# DASH_V_3_LEDS_POWER.net
KiCad netlist of a schematic drawn in Altium Designer
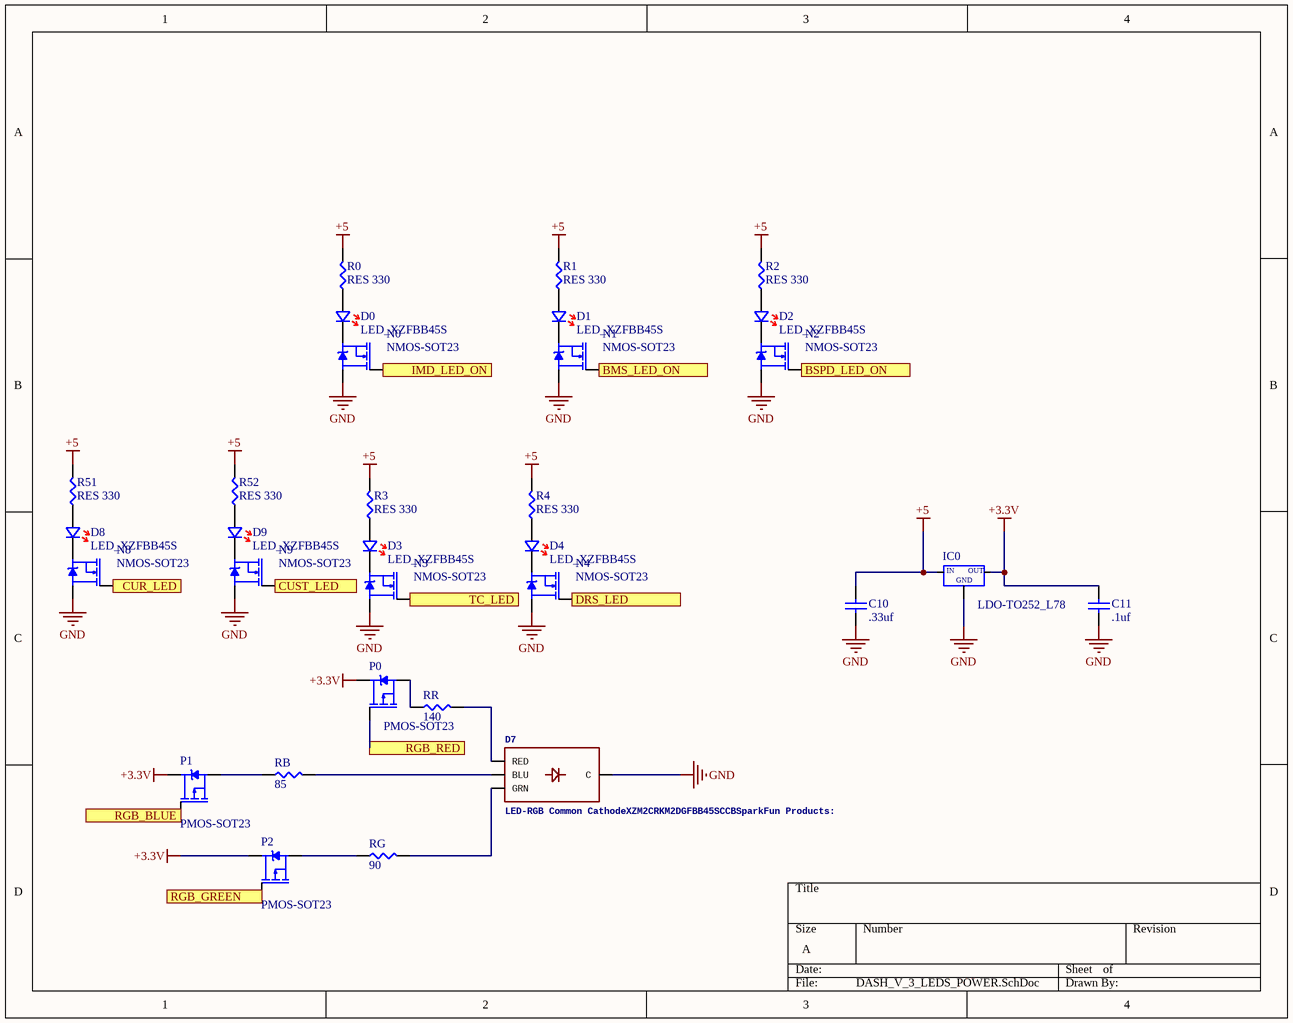
[diagram p0: DASH_V_3_LEDS_POWER.SchDoc]

(export (version "E")
  (design (tool "Eeschema 10.0.6"))
  (components
    (comp (ref "C10")
      (value ".33uf")
      (footprint "CAPC1608X87X35NL15T15")
      (description ".1 uf")
      (fields (field (name "PART NUMBER") "C0603C104J3RAC7867") (field (name "MANUFACTURER") "Kemet"))
      (libsource (lib "Altium Content Vault") (part "CAP"))
    )
    (comp (ref "C11")
      (value ".1uf")
      (footprint "CAPC1608X87X35NL15T15")
      (description ".1 uf")
      (fields (field (name "PART NUMBER") "C0603C104J3RAC7867") (field (name "MANUFACTURER") "Kemet"))
      (libsource (lib "Altium Content Vault") (part "CAP"))
    )
    (comp (ref "D0")
      (value "LED_XZFBB45S")
      (footprint "LED_XZFBB45S")
      (libsource (lib "ife19_Elec_Library") (part "LED_XZFBB45S"))
    )
    (comp (ref "D1")
      (value "LED_XZFBB45S")
      (footprint "LED_XZFBB45S")
      (libsource (lib "ife19_Elec_Library") (part "LED_XZFBB45S"))
    )
    (comp (ref "D2")
      (value "LED_XZFBB45S")
      (footprint "LED_XZFBB45S")
      (libsource (lib "ife19_Elec_Library") (part "LED_XZFBB45S"))
    )
    (comp (ref "D3")
      (value "LED_XZFBB45S")
      (footprint "LED_XZFBB45S")
      (libsource (lib "ife19_Elec_Library") (part "LED_XZFBB45S"))
    )
    (comp (ref "D4")
      (value "LED_XZFBB45S")
      (footprint "LED_XZFBB45S")
      (libsource (lib "ife19_Elec_Library") (part "LED_XZFBB45S"))
    )
    (comp (ref "D7")
      (value "LED-RGB Common CathodeXZM2CRKM2DGFBB45SCCBSparkFun Products:")
      (footprint "PLCC4SMDLED")
      (libsource (lib "SparkFun-LED") (part "SUNLEDSMD1"))
    )
    (comp (ref "D8")
      (value "LED_XZFBB45S")
      (footprint "LED_XZFBB45S")
      (libsource (lib "ife19_Elec_Library") (part "LED_XZFBB45S"))
    )
    (comp (ref "D9")
      (value "LED_XZFBB45S")
      (footprint "LED_XZFBB45S")
      (libsource (lib "ife19_Elec_Library") (part "LED_XZFBB45S"))
    )
    (comp (ref "IC0")
      (value "LDO-TO252_L78")
      (footprint "TO252")
      (libsource (lib "ife19_Elec_Library") (part "LDO-TO252_L78"))
    )
    (comp (ref "N0")
      (value "NMOS-SOT23")
      (footprint "SOT23")
      (libsource (lib "ife19_Elec_Library") (part "NMOS-SOT23"))
    )
    (comp (ref "N1")
      (value "NMOS-SOT23")
      (footprint "SOT23")
      (libsource (lib "ife19_Elec_Library") (part "NMOS-SOT23"))
    )
    (comp (ref "N2")
      (value "NMOS-SOT23")
      (footprint "SOT23")
      (libsource (lib "ife19_Elec_Library") (part "NMOS-SOT23"))
    )
    (comp (ref "N3")
      (value "NMOS-SOT23")
      (footprint "SOT23")
      (libsource (lib "ife19_Elec_Library") (part "NMOS-SOT23"))
    )
    (comp (ref "N4")
      (value "NMOS-SOT23")
      (footprint "SOT23")
      (libsource (lib "ife19_Elec_Library") (part "NMOS-SOT23"))
    )
    (comp (ref "N8")
      (value "NMOS-SOT23")
      (footprint "SOT23")
      (libsource (lib "ife19_Elec_Library") (part "NMOS-SOT23"))
    )
    (comp (ref "N9")
      (value "NMOS-SOT23")
      (footprint "SOT23")
      (libsource (lib "ife19_Elec_Library") (part "NMOS-SOT23"))
    )
    (comp (ref "P0")
      (value "PMOS-SOT23")
      (footprint "SOT23")
      (libsource (lib "ife19_Elec_Library") (part "PMOS-SOT23"))
    )
    (comp (ref "P1")
      (value "PMOS-SOT23")
      (footprint "SOT23")
      (libsource (lib "ife19_Elec_Library") (part "PMOS-SOT23"))
    )
    (comp (ref "P2")
      (value "PMOS-SOT23")
      (footprint "SOT23")
      (libsource (lib "ife19_Elec_Library") (part "PMOS-SOT23"))
    )
    (comp (ref "R0")
      (value "RES 330")
      (footprint "RES-0603")
      (libsource (lib "ife19_Elec_Library") (part "RES-0603"))
    )
    (comp (ref "R1")
      (value "RES 330")
      (footprint "RES-0603")
      (libsource (lib "ife19_Elec_Library") (part "RES-0603"))
    )
    (comp (ref "R2")
      (value "RES 330")
      (footprint "RES-0603")
      (libsource (lib "ife19_Elec_Library") (part "RES-0603"))
    )
    (comp (ref "R3")
      (value "RES 330")
      (footprint "RES-0603")
      (libsource (lib "ife19_Elec_Library") (part "RES-0603"))
    )
    (comp (ref "R4")
      (value "RES 330")
      (footprint "RES-0603")
      (libsource (lib "ife19_Elec_Library") (part "RES-0603"))
    )
    (comp (ref "R51")
      (value "RES 330")
      (footprint "RES-0603")
      (libsource (lib "ife19_Elec_Library") (part "RES-0603"))
    )
    (comp (ref "R52")
      (value "RES 330")
      (footprint "RES-0603")
      (libsource (lib "ife19_Elec_Library") (part "RES-0603"))
    )
    (comp (ref "RB")
      (value "85")
      (footprint "RES-0603")
      (libsource (lib "ife19_Elec_Library") (part "RES-0603"))
    )
    (comp (ref "RG")
      (value "90")
      (footprint "RES-0603")
      (libsource (lib "ife19_Elec_Library") (part "RES-0603"))
    )
    (comp (ref "RR")
      (value "140")
      (footprint "RES-0603")
      (libsource (lib "ife19_Elec_Library") (part "RES-0603"))
    )
  )
  (nets
    (net (code "1") (name "+3.3V") (class "Default")
      (node (ref "C11") (pin "2") (pinfunction "2_2") (pintype "passive"))
      (node (ref "IC0") (pin "3") (pinfunction "22_3") (pintype "passive"))
      (node (ref "P0") (pin "2") (pinfunction "S_2") (pintype "passive"))
      (node (ref "P1") (pin "2") (pinfunction "S_2") (pintype "passive"))
      (node (ref "P2") (pin "2") (pinfunction "S_2") (pintype "passive"))
    )
    (net (code "2") (name "+5") (class "Default")
      (node (ref "C10") (pin "2") (pinfunction "2_2") (pintype "passive"))
      (node (ref "IC0") (pin "1") (pinfunction "21_1") (pintype "passive"))
      (node (ref "R0") (pin "2") (pinfunction "2_2") (pintype "passive"))
      (node (ref "R1") (pin "2") (pinfunction "2_2") (pintype "passive"))
      (node (ref "R2") (pin "2") (pinfunction "2_2") (pintype "passive"))
      (node (ref "R3") (pin "2") (pinfunction "2_2") (pintype "passive"))
      (node (ref "R4") (pin "2") (pinfunction "2_2") (pintype "passive"))
      (node (ref "R51") (pin "2") (pinfunction "2_2") (pintype "passive"))
      (node (ref "R52") (pin "2") (pinfunction "2_2") (pintype "passive"))
    )
    (net (code "3") (name "/BMS_LED_ON") (class "Default")
      (node (ref "N1") (pin "1") (pinfunction "G_1") (pintype "passive"))
    )
    (net (code "4") (name "/BSPD_LED_ON") (class "Default")
      (node (ref "N2") (pin "1") (pinfunction "G_1") (pintype "passive"))
    )
    (net (code "5") (name "/CUR_LED") (class "Default")
      (node (ref "N8") (pin "1") (pinfunction "G_1") (pintype "passive"))
    )
    (net (code "6") (name "/CUST_LED") (class "Default")
      (node (ref "N9") (pin "1") (pinfunction "G_1") (pintype "passive"))
    )
    (net (code "7") (name "/DRS_LED") (class "Default")
      (node (ref "N4") (pin "1") (pinfunction "G_1") (pintype "passive"))
    )
    (net (code "8") (name "/IMD_LED_ON") (class "Default")
      (node (ref "N0") (pin "1") (pinfunction "G_1") (pintype "passive"))
    )
    (net (code "9") (name "/RGB_BLUE") (class "Default")
      (node (ref "P1") (pin "1") (pinfunction "G_1") (pintype "passive"))
    )
    (net (code "10") (name "/RGB_GREEN") (class "Default")
      (node (ref "P2") (pin "1") (pinfunction "G_1") (pintype "passive"))
    )
    (net (code "11") (name "/RGB_RED") (class "Default")
      (node (ref "P0") (pin "1") (pinfunction "G_1") (pintype "passive"))
    )
    (net (code "12") (name "/TC_LED") (class "Default")
      (node (ref "N3") (pin "1") (pinfunction "G_1") (pintype "passive"))
    )
    (net (code "13") (name "GND") (class "Default")
      (node (ref "C10") (pin "1") (pinfunction "1_1") (pintype "passive"))
      (node (ref "C11") (pin "1") (pinfunction "1_1") (pintype "passive"))
      (node (ref "D7") (pin "4") (pinfunction "C_4") (pintype "passive"))
      (node (ref "IC0") (pin "2") (pinfunction "23_2") (pintype "passive"))
      (node (ref "N0") (pin "2") (pinfunction "S_2") (pintype "passive"))
      (node (ref "N1") (pin "2") (pinfunction "S_2") (pintype "passive"))
      (node (ref "N2") (pin "2") (pinfunction "S_2") (pintype "passive"))
      (node (ref "N3") (pin "2") (pinfunction "S_2") (pintype "passive"))
      (node (ref "N4") (pin "2") (pinfunction "S_2") (pintype "passive"))
      (node (ref "N8") (pin "2") (pinfunction "S_2") (pintype "passive"))
      (node (ref "N9") (pin "2") (pinfunction "S_2") (pintype "passive"))
    )
    (net (code "14") (name "Net-(D0-PadA)") (class "Default")
      (node (ref "D0") (pin "A") (pinfunction "A_A") (pintype "passive"))
      (node (ref "R0") (pin "1") (pinfunction "1_1") (pintype "passive"))
    )
    (net (code "15") (name "Net-(D1-PadA)") (class "Default")
      (node (ref "D1") (pin "A") (pinfunction "A_A") (pintype "passive"))
      (node (ref "R1") (pin "1") (pinfunction "1_1") (pintype "passive"))
    )
    (net (code "16") (name "Net-(D2-PadA)") (class "Default")
      (node (ref "D2") (pin "A") (pinfunction "A_A") (pintype "passive"))
      (node (ref "R2") (pin "1") (pinfunction "1_1") (pintype "passive"))
    )
    (net (code "17") (name "Net-(D3-PadA)") (class "Default")
      (node (ref "D3") (pin "A") (pinfunction "A_A") (pintype "passive"))
      (node (ref "R3") (pin "1") (pinfunction "1_1") (pintype "passive"))
    )
    (net (code "18") (name "Net-(D4-PadA)") (class "Default")
      (node (ref "D4") (pin "A") (pinfunction "A_A") (pintype "passive"))
      (node (ref "R4") (pin "1") (pinfunction "1_1") (pintype "passive"))
    )
    (net (code "19") (name "Net-(D7-BLU)") (class "Default")
      (node (ref "D7") (pin "3") (pinfunction "BLU_3") (pintype "passive"))
      (node (ref "RB") (pin "2") (pinfunction "2_2") (pintype "passive"))
    )
    (net (code "20") (name "Net-(D7-GRN)") (class "Default")
      (node (ref "D7") (pin "2") (pinfunction "GRN_2") (pintype "passive"))
      (node (ref "RG") (pin "2") (pinfunction "2_2") (pintype "passive"))
    )
    (net (code "21") (name "Net-(D7-RED)") (class "Default")
      (node (ref "D7") (pin "1") (pinfunction "RED_1") (pintype "passive"))
      (node (ref "RR") (pin "2") (pinfunction "2_2") (pintype "passive"))
    )
    (net (code "22") (name "Net-(D8-PadA)") (class "Default")
      (node (ref "D8") (pin "A") (pinfunction "A_A") (pintype "passive"))
      (node (ref "R51") (pin "1") (pinfunction "1_1") (pintype "passive"))
    )
    (net (code "23") (name "Net-(D9-PadA)") (class "Default")
      (node (ref "D9") (pin "A") (pinfunction "A_A") (pintype "passive"))
      (node (ref "R52") (pin "1") (pinfunction "1_1") (pintype "passive"))
    )
    (net (code "24") (name "Net-(N0-D)") (class "Default")
      (node (ref "D0") (pin "K") (pinfunction "K_K") (pintype "passive"))
      (node (ref "N0") (pin "3") (pinfunction "D_3") (pintype "passive"))
    )
    (net (code "25") (name "Net-(N1-D)") (class "Default")
      (node (ref "D1") (pin "K") (pinfunction "K_K") (pintype "passive"))
      (node (ref "N1") (pin "3") (pinfunction "D_3") (pintype "passive"))
    )
    (net (code "26") (name "Net-(N2-D)") (class "Default")
      (node (ref "D2") (pin "K") (pinfunction "K_K") (pintype "passive"))
      (node (ref "N2") (pin "3") (pinfunction "D_3") (pintype "passive"))
    )
    (net (code "27") (name "Net-(N3-D)") (class "Default")
      (node (ref "D3") (pin "K") (pinfunction "K_K") (pintype "passive"))
      (node (ref "N3") (pin "3") (pinfunction "D_3") (pintype "passive"))
    )
    (net (code "28") (name "Net-(N4-D)") (class "Default")
      (node (ref "D4") (pin "K") (pinfunction "K_K") (pintype "passive"))
      (node (ref "N4") (pin "3") (pinfunction "D_3") (pintype "passive"))
    )
    (net (code "29") (name "Net-(N8-D)") (class "Default")
      (node (ref "D8") (pin "K") (pinfunction "K_K") (pintype "passive"))
      (node (ref "N8") (pin "3") (pinfunction "D_3") (pintype "passive"))
    )
    (net (code "30") (name "Net-(N9-D)") (class "Default")
      (node (ref "D9") (pin "K") (pinfunction "K_K") (pintype "passive"))
      (node (ref "N9") (pin "3") (pinfunction "D_3") (pintype "passive"))
    )
    (net (code "31") (name "Net-(P0-D)") (class "Default")
      (node (ref "P0") (pin "3") (pinfunction "D_3") (pintype "passive"))
      (node (ref "RR") (pin "1") (pinfunction "1_1") (pintype "passive"))
    )
    (net (code "32") (name "Net-(P1-D)") (class "Default")
      (node (ref "P1") (pin "3") (pinfunction "D_3") (pintype "passive"))
      (node (ref "RB") (pin "1") (pinfunction "1_1") (pintype "passive"))
    )
    (net (code "33") (name "Net-(P2-D)") (class "Default")
      (node (ref "P2") (pin "3") (pinfunction "D_3") (pintype "passive"))
      (node (ref "RG") (pin "1") (pinfunction "1_1") (pintype "passive"))
    )
  )
)
